# 1-Schematic_ACS2STM-alt-IDC.net
KiCad netlist of a schematic drawn in EasyEDA
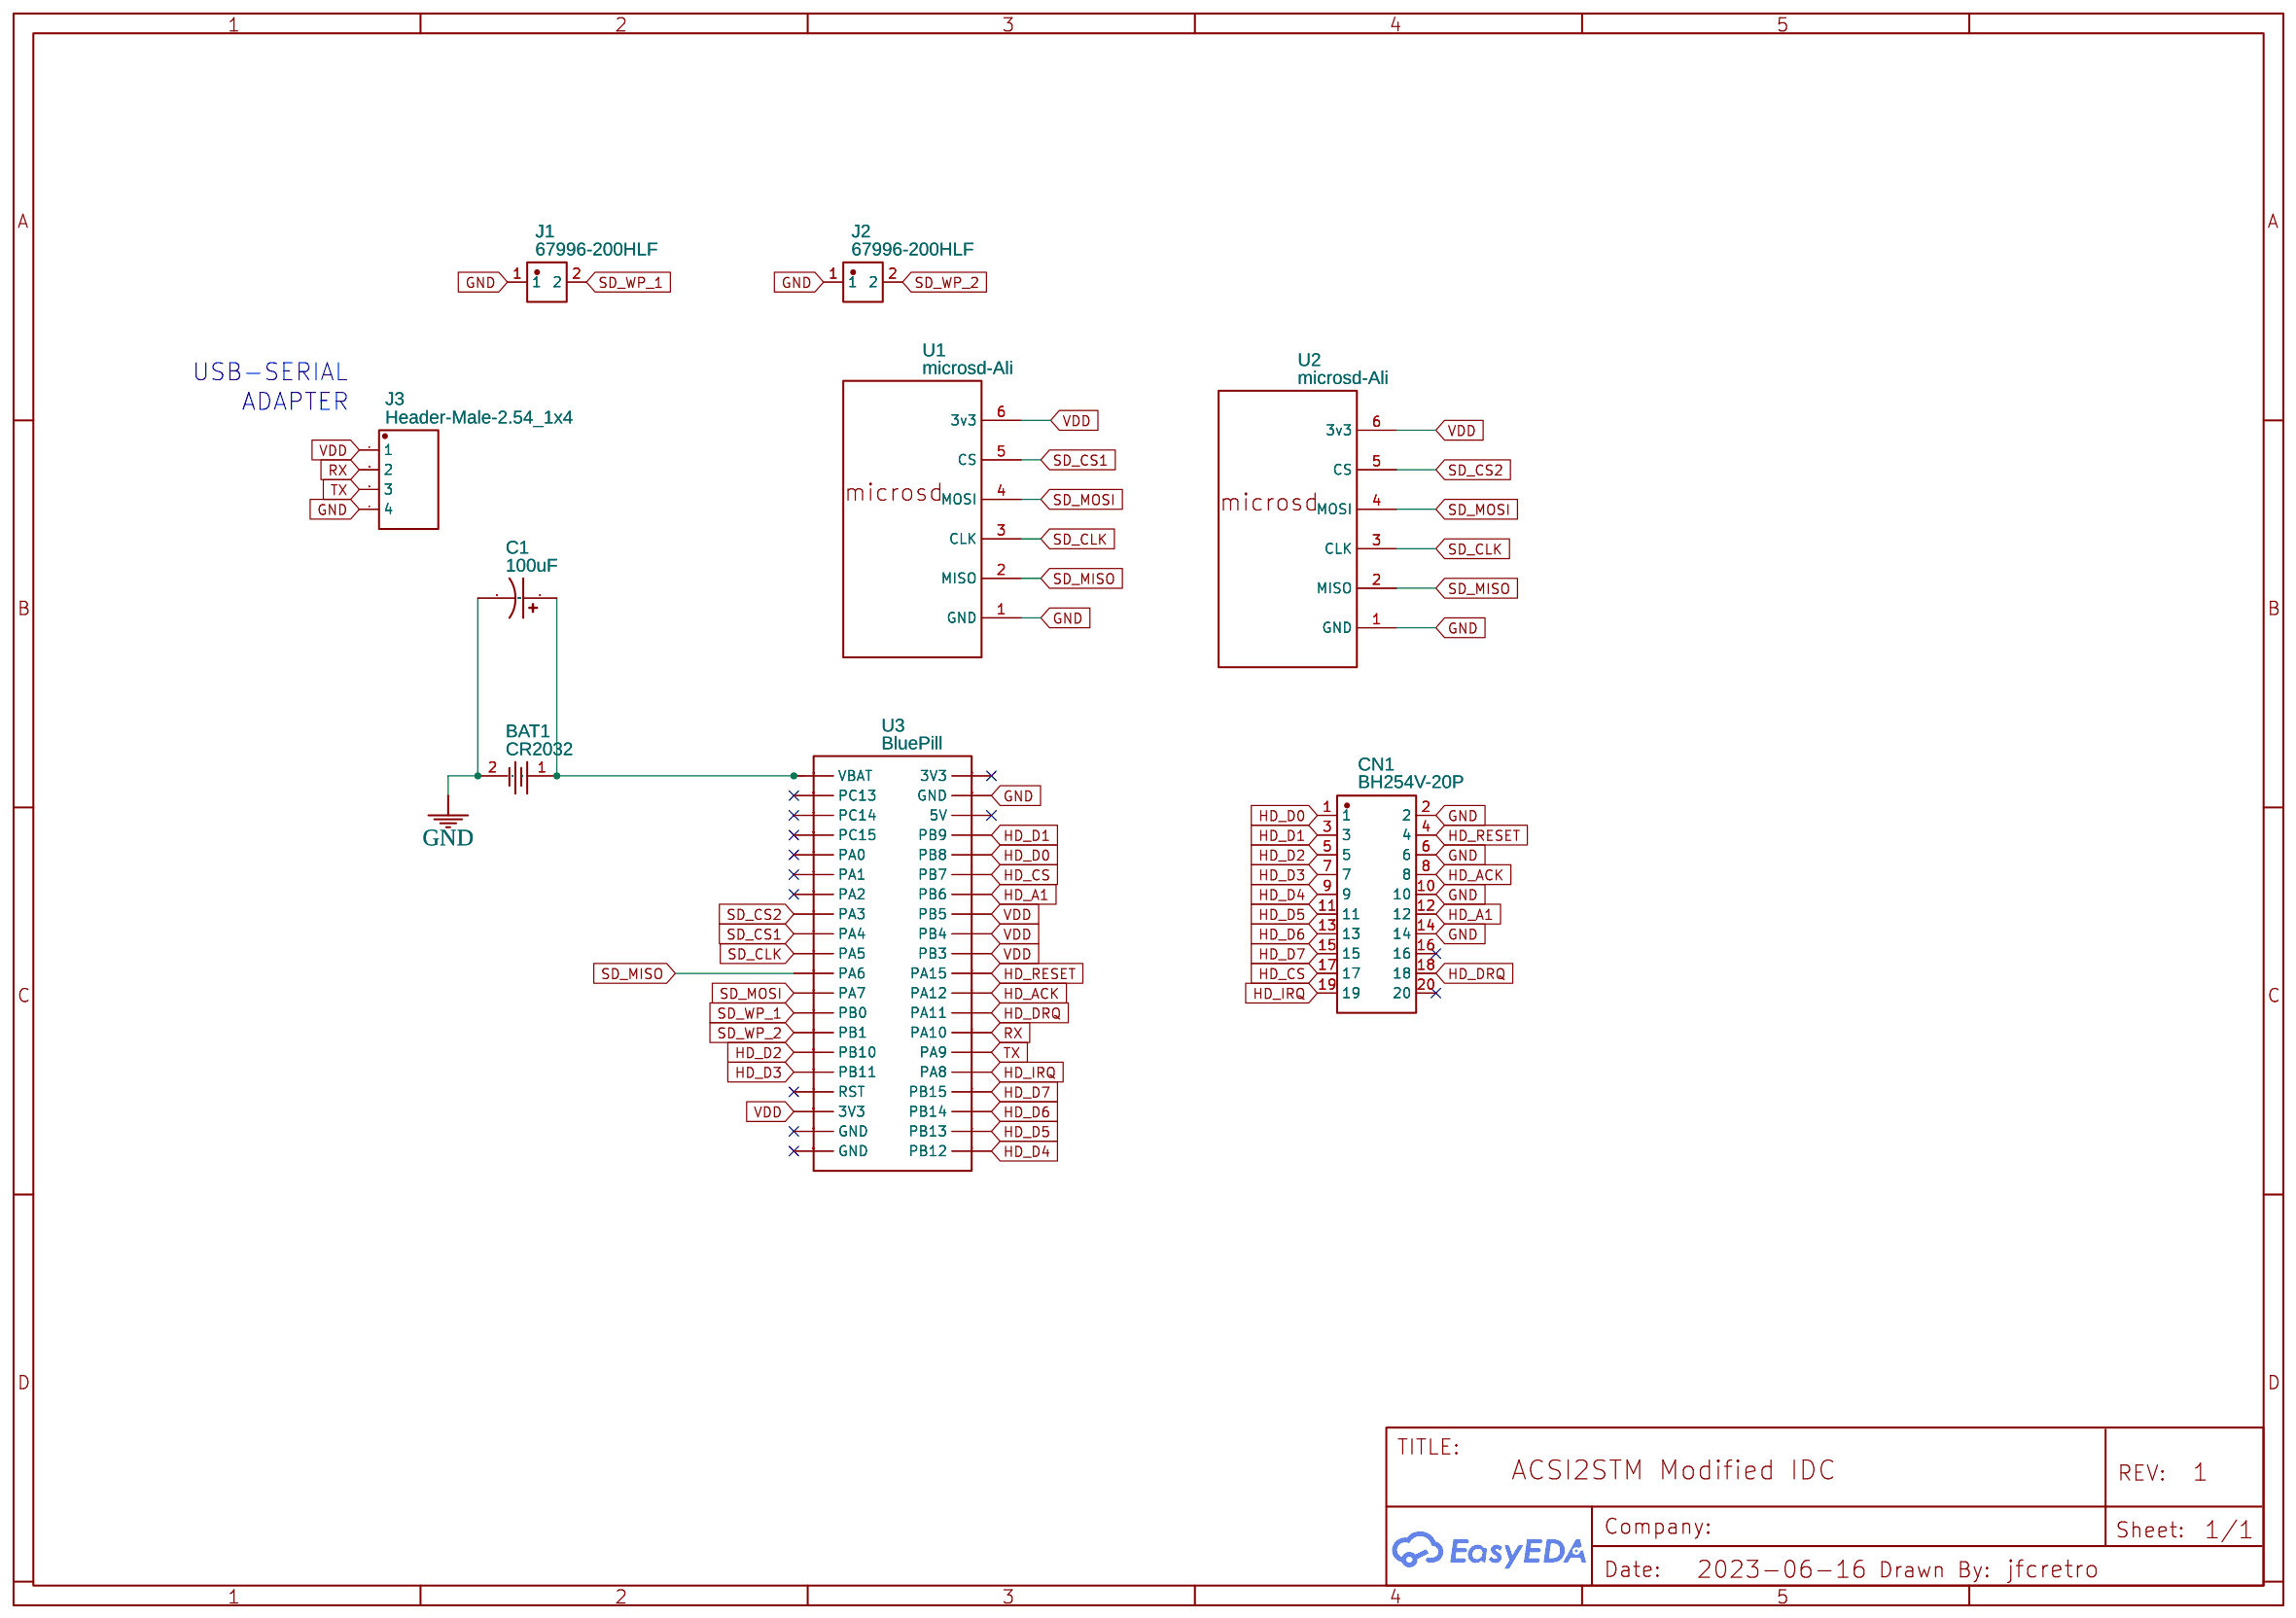
[diagram p0: schematic sheet]

(export (version "E")
  (design (tool "Eeschema 10.0.6"))
  (components
    (comp (ref "BAT1")
      (value "CR2032")
      (fields (field (name "BOM_Supplier Part") "C9900007674"))
      (libsource (lib "") (part "CR2032_C9900007674"))
    )
    (comp (ref "C1") (value "100uF") (libsource (lib "") (part "CE_TH_D6.3×F2.5_US")))
    (comp (ref "CN1")
      (value "BH254V-20P")
      (fields (field (name "BOM_Supplier Part") "C492444"))
      (libsource (lib "") (part "BH254V-20P"))
    )
    (comp (ref "J1")
      (value "67996-200HLF")
      (fields (field (name "BOM_Supplier Part") "C236045"))
      (libsource (lib "") (part "67996-200HLF"))
    )
    (comp (ref "J2")
      (value "67996-200HLF")
      (fields (field (name "BOM_Supplier Part") "C236045"))
      (libsource (lib "") (part "67996-200HLF"))
    )
    (comp (ref "J3")
      (value "Header-Male-2.54_1x4")
      (fields
        (field (name "BOM_Manufacturer Part") "B-2100S04P-A110")
        (field (name "BOM_Supplier Part") "C124378")
      )
      (libsource (lib "") (part "Header-Male-2.54_1x4"))
    )
    (comp (ref "U1") (value "microsd-Ali") (libsource (lib "") (part "microsd-Ali")))
    (comp (ref "U2") (value "microsd-Ali") (libsource (lib "") (part "microsd-Ali")))
    (comp (ref "U3") (value "BluePill") (libsource (lib "") (part "BluePill")))
  )
  (nets
    (net (code "1") (name "GND") (class "Default")
      (node (ref "BAT1") (pin "2") (pinfunction "2_2") (pintype "input"))
      (node (ref "C1") (pin "2") (pinfunction "2_2") (pintype "unspecified"))
      (node (ref "CN1") (pin "10") (pinfunction "10_10") (pintype "unspecified"))
      (node (ref "CN1") (pin "14") (pinfunction "14_14") (pintype "unspecified"))
      (node (ref "CN1") (pin "2") (pinfunction "2_2") (pintype "unspecified"))
      (node (ref "CN1") (pin "6") (pinfunction "6_6") (pintype "unspecified"))
      (node (ref "J1") (pin "1") (pinfunction "1_1") (pintype "unspecified"))
      (node (ref "J2") (pin "1") (pinfunction "1_1") (pintype "unspecified"))
      (node (ref "J3") (pin "4") (pinfunction "4_4") (pintype "unspecified"))
      (node (ref "U1") (pin "1") (pinfunction "GND_1") (pintype "unspecified"))
      (node (ref "U2") (pin "1") (pinfunction "GND_1") (pintype "unspecified"))
      (node (ref "U3") (pin "GND_3") (pinfunction "GND_GND_3") (pintype "unspecified"))
    )
    (net (code "2") (name "HD_A1") (class "Default")
      (node (ref "CN1") (pin "12") (pinfunction "12_12") (pintype "unspecified"))
      (node (ref "U3") (pin "PB6") (pinfunction "PB6_PB6") (pintype "unspecified"))
    )
    (net (code "3") (name "HD_ACK") (class "Default")
      (node (ref "CN1") (pin "8") (pinfunction "8_8") (pintype "unspecified"))
      (node (ref "U3") (pin "PA12") (pinfunction "PA12_PA12") (pintype "unspecified"))
    )
    (net (code "4") (name "HD_CS") (class "Default")
      (node (ref "CN1") (pin "17") (pinfunction "17_17") (pintype "unspecified"))
      (node (ref "U3") (pin "PB7") (pinfunction "PB7_PB7") (pintype "unspecified"))
    )
    (net (code "5") (name "HD_D0") (class "Default")
      (node (ref "CN1") (pin "1") (pinfunction "1_1") (pintype "unspecified"))
      (node (ref "U3") (pin "PB8") (pinfunction "PB8_PB8") (pintype "unspecified"))
    )
    (net (code "6") (name "HD_D1") (class "Default")
      (node (ref "CN1") (pin "3") (pinfunction "3_3") (pintype "unspecified"))
      (node (ref "U3") (pin "PB9") (pinfunction "PB9_PB9") (pintype "unspecified"))
    )
    (net (code "7") (name "HD_D2") (class "Default")
      (node (ref "CN1") (pin "5") (pinfunction "5_5") (pintype "unspecified"))
      (node (ref "U3") (pin "PB10") (pinfunction "PB10_PB10") (pintype "unspecified"))
    )
    (net (code "8") (name "HD_D3") (class "Default")
      (node (ref "CN1") (pin "7") (pinfunction "7_7") (pintype "unspecified"))
      (node (ref "U3") (pin "PB11") (pinfunction "PB11_PB11") (pintype "unspecified"))
    )
    (net (code "9") (name "HD_D4") (class "Default")
      (node (ref "CN1") (pin "9") (pinfunction "9_9") (pintype "unspecified"))
      (node (ref "U3") (pin "PB12") (pinfunction "PB12_PB12") (pintype "unspecified"))
    )
    (net (code "10") (name "HD_D5") (class "Default")
      (node (ref "CN1") (pin "11") (pinfunction "11_11") (pintype "unspecified"))
      (node (ref "U3") (pin "PB13") (pinfunction "PB13_PB13") (pintype "unspecified"))
    )
    (net (code "11") (name "HD_D6") (class "Default")
      (node (ref "CN1") (pin "13") (pinfunction "13_13") (pintype "unspecified"))
      (node (ref "U3") (pin "PB14") (pinfunction "PB14_PB14") (pintype "unspecified"))
    )
    (net (code "12") (name "HD_D7") (class "Default")
      (node (ref "CN1") (pin "15") (pinfunction "15_15") (pintype "unspecified"))
      (node (ref "U3") (pin "PB15") (pinfunction "PB15_PB15") (pintype "unspecified"))
    )
    (net (code "13") (name "HD_DRQ") (class "Default")
      (node (ref "CN1") (pin "18") (pinfunction "18_18") (pintype "unspecified"))
      (node (ref "U3") (pin "PA11") (pinfunction "PA11_PA11") (pintype "unspecified"))
    )
    (net (code "14") (name "HD_IRQ") (class "Default")
      (node (ref "CN1") (pin "19") (pinfunction "19_19") (pintype "unspecified"))
      (node (ref "U3") (pin "PA8") (pinfunction "PA8_PA8") (pintype "unspecified"))
    )
    (net (code "15") (name "HD_RESET") (class "Default")
      (node (ref "CN1") (pin "4") (pinfunction "4_4") (pintype "unspecified"))
      (node (ref "U3") (pin "PA15") (pinfunction "PA15_PA15") (pintype "unspecified"))
    )
    (net (code "16") (name "Net-(BAT1-Pad1)") (class "Default")
      (node (ref "BAT1") (pin "1") (pinfunction "1_1") (pintype "input"))
      (node (ref "C1") (pin "1") (pinfunction "1_1") (pintype "unspecified"))
      (node (ref "U3") (pin "VBAT") (pinfunction "VBAT_VBAT") (pintype "unspecified"))
    )
    (net (code "17") (name "RX") (class "Default")
      (node (ref "J3") (pin "2") (pinfunction "2_2") (pintype "unspecified"))
      (node (ref "U3") (pin "PA10") (pinfunction "PA10_PA10") (pintype "unspecified"))
    )
    (net (code "18") (name "SD_CLK") (class "Default")
      (node (ref "U1") (pin "3") (pinfunction "CLK_3") (pintype "unspecified"))
      (node (ref "U2") (pin "3") (pinfunction "CLK_3") (pintype "unspecified"))
      (node (ref "U3") (pin "PA5") (pinfunction "PA5_PA5") (pintype "unspecified"))
    )
    (net (code "19") (name "SD_CS1") (class "Default")
      (node (ref "U1") (pin "5") (pinfunction "CS_5") (pintype "unspecified"))
      (node (ref "U3") (pin "PA4") (pinfunction "PA4_PA4") (pintype "unspecified"))
    )
    (net (code "20") (name "SD_CS2") (class "Default")
      (node (ref "U2") (pin "5") (pinfunction "CS_5") (pintype "unspecified"))
      (node (ref "U3") (pin "PA3") (pinfunction "PA3_PA3") (pintype "unspecified"))
    )
    (net (code "21") (name "SD_MISO") (class "Default")
      (node (ref "U1") (pin "2") (pinfunction "MISO_2") (pintype "unspecified"))
      (node (ref "U2") (pin "2") (pinfunction "MISO_2") (pintype "unspecified"))
      (node (ref "U3") (pin "PA6") (pinfunction "PA6_PA6") (pintype "unspecified"))
    )
    (net (code "22") (name "SD_MOSI") (class "Default")
      (node (ref "U1") (pin "4") (pinfunction "MOSI_4") (pintype "unspecified"))
      (node (ref "U2") (pin "4") (pinfunction "MOSI_4") (pintype "unspecified"))
      (node (ref "U3") (pin "PA7") (pinfunction "PA7_PA7") (pintype "unspecified"))
    )
    (net (code "23") (name "SD_WP_1") (class "Default")
      (node (ref "J1") (pin "2") (pinfunction "2_2") (pintype "unspecified"))
      (node (ref "U3") (pin "PB0") (pinfunction "PB0_PB0") (pintype "unspecified"))
    )
    (net (code "24") (name "SD_WP_2") (class "Default")
      (node (ref "J2") (pin "2") (pinfunction "2_2") (pintype "unspecified"))
      (node (ref "U3") (pin "PB1") (pinfunction "PB1_PB1") (pintype "unspecified"))
    )
    (net (code "25") (name "TX") (class "Default")
      (node (ref "J3") (pin "3") (pinfunction "3_3") (pintype "unspecified"))
      (node (ref "U3") (pin "PA9") (pinfunction "PA9_PA9") (pintype "unspecified"))
    )
    (net (code "26") (name "VDD") (class "Default")
      (node (ref "J3") (pin "1") (pinfunction "1_1") (pintype "unspecified"))
      (node (ref "U1") (pin "6") (pinfunction "3v3_6") (pintype "unspecified"))
      (node (ref "U2") (pin "6") (pinfunction "3v3_6") (pintype "unspecified"))
      (node (ref "U3") (pin "3V3_1") (pinfunction "3V3_3V3_1") (pintype "unspecified"))
      (node (ref "U3") (pin "PB3") (pinfunction "PB3_PB3") (pintype "unspecified"))
      (node (ref "U3") (pin "PB4") (pinfunction "PB4_PB4") (pintype "unspecified"))
      (node (ref "U3") (pin "PB5") (pinfunction "PB5_PB5") (pintype "unspecified"))
    )
    (net (code "27") (name "unconnected-(CN1-Pad16)") (class "Default")
      (node (ref "CN1") (pin "16") (pinfunction "16_16") (pintype "unspecified+no_connect"))
    )
    (net (code "28") (name "unconnected-(CN1-Pad20)") (class "Default")
      (node (ref "CN1") (pin "20") (pinfunction "20_20") (pintype "unspecified+no_connect"))
    )
    (net (code "29") (name "unconnected-(U3-3V3-Pad3V3_2)") (class "Default")
      (node (ref "U3") (pin "3V3_2") (pinfunction "3V3_3V3_2") (pintype "unspecified+no_connect"))
    )
    (net (code "30") (name "unconnected-(U3-GND-PadGND_1)") (class "Default")
      (node (ref "U3") (pin "GND_1") (pinfunction "GND_GND_1") (pintype "unspecified+no_connect"))
    )
    (net (code "31") (name "unconnected-(U3-GND-PadGND_2)") (class "Default")
      (node (ref "U3") (pin "GND_2") (pinfunction "GND_GND_2") (pintype "unspecified+no_connect"))
    )
    (net (code "32") (name "unconnected-(U3-Pad5V)") (class "Default")
      (node (ref "U3") (pin "5V") (pinfunction "5V_5V") (pintype "unspecified+no_connect"))
    )
    (net (code "33") (name "unconnected-(U3-PadPA0)") (class "Default")
      (node (ref "U3") (pin "PA0") (pinfunction "PA0_PA0") (pintype "unspecified+no_connect"))
    )
    (net (code "34") (name "unconnected-(U3-PadPA1)") (class "Default")
      (node (ref "U3") (pin "PA1") (pinfunction "PA1_PA1") (pintype "unspecified+no_connect"))
    )
    (net (code "35") (name "unconnected-(U3-PadPA2)") (class "Default")
      (node (ref "U3") (pin "PA2") (pinfunction "PA2_PA2") (pintype "unspecified+no_connect"))
    )
    (net (code "36") (name "unconnected-(U3-PadPC13)") (class "Default")
      (node (ref "U3") (pin "PC13") (pinfunction "PC13_PC13") (pintype "unspecified+no_connect"))
    )
    (net (code "37") (name "unconnected-(U3-PadPC14)") (class "Default")
      (node (ref "U3") (pin "PC14") (pinfunction "PC14_PC14") (pintype "unspecified+no_connect"))
    )
    (net (code "38") (name "unconnected-(U3-PadPC15)") (class "Default")
      (node (ref "U3") (pin "PC15") (pinfunction "PC15_PC15") (pintype "unspecified+no_connect"))
    )
    (net (code "39") (name "unconnected-(U3-PadRST)") (class "Default")
      (node (ref "U3") (pin "RST") (pinfunction "RST_RST") (pintype "unspecified+no_connect"))
    )
  )
)
